# ECG.net
KiCad netlist of a schematic drawn in EAGLE
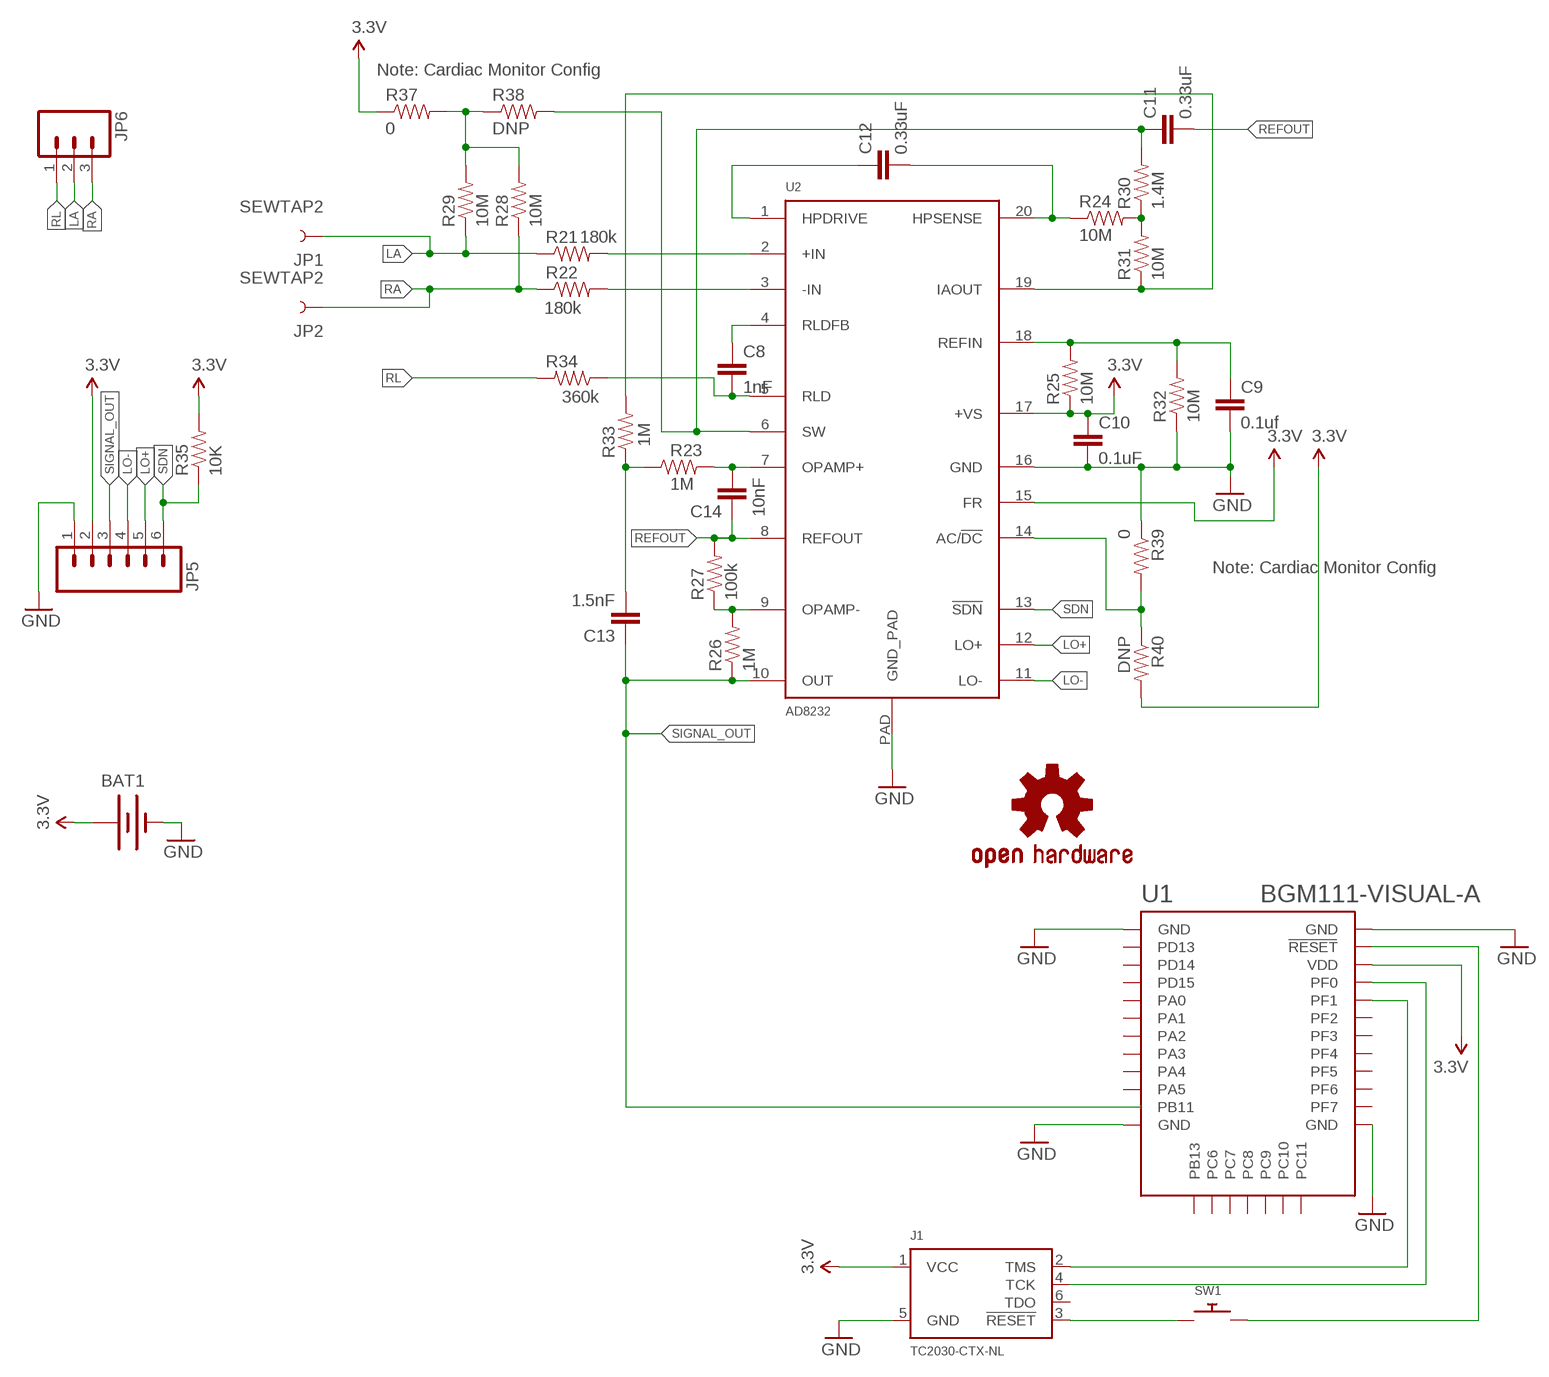
[diagram p0: schematic, sheet 1]

(export (version "E")
  (design (tool "Eeschema 10.0.6"))
  (components
    (comp (ref "BAT1")
      (value "BATTERY20SMD")
      (footprint "eagle-import:BATTCON_20MM")
      (libsource (lib "eagle-import") (part "BATTERY20SMD"))
    )
    (comp (ref "C8")
      (value "1nF")
      (footprint "eagle-import:0603-CAP")
      (libsource (lib "eagle-import") (part "CAP0603-CAP"))
    )
    (comp (ref "C9")
      (value "0.1uf")
      (footprint "eagle-import:0603-CAP")
      (libsource (lib "eagle-import") (part "CAP0603-CAP"))
    )
    (comp (ref "C10")
      (value "0.1uF")
      (footprint "eagle-import:0603-CAP")
      (libsource (lib "eagle-import") (part "CAP0603-CAP"))
    )
    (comp (ref "C11")
      (value "0.33uF")
      (footprint "eagle-import:0805")
      (libsource (lib "eagle-import") (part "CAP0805"))
    )
    (comp (ref "C12")
      (value "0.33uF")
      (footprint "eagle-import:0805")
      (libsource (lib "eagle-import") (part "CAP0805"))
    )
    (comp (ref "C13")
      (value "1.5nF")
      (footprint "eagle-import:0603-CAP")
      (libsource (lib "eagle-import") (part "CAP0603-CAP"))
    )
    (comp (ref "C14")
      (value "10nF")
      (footprint "eagle-import:0603-CAP")
      (libsource (lib "eagle-import") (part "CAP0603-CAP"))
    )
    (comp (ref "J1")
      (value "TC2030-CTX-NL")
      (footprint "eagle-import:TC2030-IDC-NL")
      (libsource (lib "eagle-import") (part "TC2030-CTX-NL"))
    )
    (comp (ref "JP1")
      (value "SEWTAP2")
      (footprint "eagle-import:PETAL-LONG-2")
      (libsource (lib "eagle-import") (part "SEWTAP2"))
    )
    (comp (ref "JP2")
      (value "SEWTAP2")
      (footprint "eagle-import:PETAL-LONG-2")
      (libsource (lib "eagle-import") (part "SEWTAP2"))
    )
    (comp (ref "JP5")
      (value "M06SIP")
      (footprint "eagle-import:1X06")
      (libsource (lib "eagle-import") (part "M06SIP"))
    )
    (comp (ref "JP6")
      (value "M03PTH")
      (footprint "eagle-import:1X03")
      (libsource (lib "eagle-import") (part "M03PTH"))
    )
    (comp (ref "LOGO3")
      (value "OSHW-LOGOS")
      (footprint "eagle-import:OSHW-LOGO-S")
      (libsource (lib "eagle-import") (part "OSHW-LOGOS"))
    )
    (comp (ref "R21")
      (value "180k")
      (footprint "eagle-import:0603-RES")
      (libsource (lib "eagle-import") (part "RESISTOR0603-RES"))
    )
    (comp (ref "R22")
      (value "180k")
      (footprint "eagle-import:0603-RES")
      (libsource (lib "eagle-import") (part "RESISTOR0603-RES"))
    )
    (comp (ref "R23")
      (value "1M")
      (footprint "eagle-import:0603-RES")
      (libsource (lib "eagle-import") (part "RESISTOR0603-RES"))
    )
    (comp (ref "R24")
      (value "10M")
      (footprint "eagle-import:0603-RES")
      (libsource (lib "eagle-import") (part "RESISTOR0603-RES"))
    )
    (comp (ref "R25")
      (value "10M")
      (footprint "eagle-import:0603-RES")
      (libsource (lib "eagle-import") (part "RESISTOR0603-RES"))
    )
    (comp (ref "R26")
      (value "1M")
      (footprint "eagle-import:0603-RES")
      (libsource (lib "eagle-import") (part "RESISTOR0603-RES"))
    )
    (comp (ref "R27")
      (value "100k")
      (footprint "eagle-import:0603-RES")
      (libsource (lib "eagle-import") (part "RESISTOR0603-RES"))
    )
    (comp (ref "R28")
      (value "10M")
      (footprint "eagle-import:0603-RES")
      (libsource (lib "eagle-import") (part "RESISTOR0603-RES"))
    )
    (comp (ref "R29")
      (value "10M")
      (footprint "eagle-import:0603-RES")
      (libsource (lib "eagle-import") (part "RESISTOR0603-RES"))
    )
    (comp (ref "R30")
      (value "1.4M")
      (footprint "eagle-import:0603-RES")
      (libsource (lib "eagle-import") (part "RESISTOR0603-RES"))
    )
    (comp (ref "R31")
      (value "10M")
      (footprint "eagle-import:0603-RES")
      (libsource (lib "eagle-import") (part "RESISTOR0603-RES"))
    )
    (comp (ref "R32")
      (value "10M")
      (footprint "eagle-import:0603-RES")
      (libsource (lib "eagle-import") (part "RESISTOR0603-RES"))
    )
    (comp (ref "R33")
      (value "1M")
      (footprint "eagle-import:0603-RES")
      (libsource (lib "eagle-import") (part "RESISTOR0603-RES"))
    )
    (comp (ref "R34")
      (value "360k")
      (footprint "eagle-import:0603-RES")
      (libsource (lib "eagle-import") (part "RESISTOR0603-RES"))
    )
    (comp (ref "R35")
      (value "10K")
      (footprint "eagle-import:0603-RES")
      (libsource (lib "eagle-import") (part "10KOHM1/10W1%(0603)0603"))
    )
    (comp (ref "R37")
      (value "0")
      (footprint "eagle-import:0603")
      (libsource (lib "eagle-import") (part "0OHM1/10W5%(0603)"))
    )
    (comp (ref "R38")
      (value "DNP")
      (footprint "eagle-import:0603")
      (libsource (lib "eagle-import") (part "0OHM1/10W5%(0603)"))
    )
    (comp (ref "R39")
      (value "0")
      (footprint "eagle-import:0603")
      (libsource (lib "eagle-import") (part "0OHM1/10W5%(0603)"))
    )
    (comp (ref "R40")
      (value "DNP")
      (footprint "eagle-import:0603")
      (libsource (lib "eagle-import") (part "0OHM1/10W5%(0603)"))
    )
    (comp (ref "SW1")
      (value "SWITCH_PUSHBUTTONSOFTTOUCHSMD_SJ")
      (footprint "eagle-import:PUSHBUTTON_SMD_SJ")
      (libsource (lib "eagle-import") (part "SWITCH_PUSHBUTTONSOFTTOUCHSMD_SJ"))
    )
    (comp (ref "U1")
      (value "BGM111-VISUAL-A")
      (footprint "eagle-import:BGM111-A")
      (libsource (lib "eagle-import") (part "BGM111-VISUAL-A"))
    )
    (comp (ref "U2")
      (value "AD8232")
      (footprint "eagle-import:LFCSP_20")
      (libsource (lib "eagle-import") (part "AD8232"))
    )
  )
  (nets
    (net (code "1") (name "3.3V") (class "Default")
      (node (ref "BAT1") (pin "1") (pinfunction "+_1") (pintype "power_in"))
      (node (ref "C10") (pin "1") (pinfunction "1_1") (pintype "passive"))
      (node (ref "J1") (pin "1") (pinfunction "VCC_1") (pintype "bidirectional"))
      (node (ref "JP5") (pin "2") (pinfunction "2_2") (pintype "passive"))
      (node (ref "R25") (pin "1") (pinfunction "1_1") (pintype "passive"))
      (node (ref "R35") (pin "2") (pinfunction "2_2") (pintype "passive"))
      (node (ref "R37") (pin "1") (pinfunction "1_1") (pintype "passive"))
      (node (ref "R40") (pin "2") (pinfunction "2_2") (pintype "passive"))
      (node (ref "U1") (pin "VDD") (pinfunction "VDD_VDD") (pintype "power_in"))
      (node (ref "U2") (pin "15") (pinfunction "FR_15") (pintype "bidirectional"))
      (node (ref "U2") (pin "17") (pinfunction "+VS_17") (pintype "bidirectional"))
    )
    (net (code "2") (name "GND") (class "Default")
      (node (ref "BAT1") (pin "2") (pinfunction "-_2") (pintype "power_in"))
      (node (ref "C10") (pin "2") (pinfunction "2_2") (pintype "passive"))
      (node (ref "C9") (pin "2") (pinfunction "2_2") (pintype "passive"))
      (node (ref "J1") (pin "5") (pinfunction "GND_5") (pintype "bidirectional"))
      (node (ref "JP5") (pin "1") (pinfunction "1_1") (pintype "passive"))
      (node (ref "R32") (pin "1") (pinfunction "1_1") (pintype "passive"))
      (node (ref "R39") (pin "1") (pinfunction "1_1") (pintype "passive"))
      (node (ref "U1") (pin "GND") (pinfunction "GND_GND") (pintype "power_in"))
      (node (ref "U1") (pin "GND@2") (pinfunction "GND_GND@2") (pintype "power_in"))
      (node (ref "U1") (pin "GND@3") (pinfunction "GND_GND@3") (pintype "power_in"))
      (node (ref "U1") (pin "GND@4") (pinfunction "GND_GND@4") (pintype "power_in"))
      (node (ref "U2") (pin "16") (pinfunction "GND_16") (pintype "bidirectional"))
      (node (ref "U2") (pin "PAD") (pinfunction "GND_PAD_PAD") (pintype "bidirectional"))
    )
    (net (code "3") (name "LA") (class "Default")
      (node (ref "JP1") (pin "1") (pinfunction "1_1") (pintype "bidirectional"))
      (node (ref "JP6") (pin "2") (pinfunction "2_2") (pintype "passive"))
      (node (ref "R21") (pin "1") (pinfunction "1_1") (pintype "passive"))
      (node (ref "R29") (pin "1") (pinfunction "1_1") (pintype "passive"))
    )
    (net (code "4") (name "LO+") (class "Default")
      (node (ref "JP5") (pin "5") (pinfunction "5_5") (pintype "passive"))
      (node (ref "U2") (pin "12") (pinfunction "LO+_12") (pintype "bidirectional"))
    )
    (net (code "5") (name "LO-") (class "Default")
      (node (ref "JP5") (pin "4") (pinfunction "4_4") (pintype "passive"))
      (node (ref "U2") (pin "11") (pinfunction "LO-_11") (pintype "bidirectional"))
    )
    (net (code "6") (name "Net-(C13-Pad2)") (class "Default")
      (node (ref "C13") (pin "2") (pinfunction "2_2") (pintype "passive"))
      (node (ref "R23") (pin "1") (pinfunction "1_1") (pintype "passive"))
      (node (ref "R33") (pin "1") (pinfunction "1_1") (pintype "passive"))
    )
    (net (code "7") (name "Net-(J1-TCK)") (class "Default")
      (node (ref "J1") (pin "4") (pinfunction "TCK_4") (pintype "bidirectional"))
      (node (ref "U1") (pin "PF0") (pinfunction "PF0_PF0") (pintype "bidirectional"))
    )
    (net (code "8") (name "Net-(J1-TMS)") (class "Default")
      (node (ref "J1") (pin "2") (pinfunction "TMS_2") (pintype "bidirectional"))
      (node (ref "U1") (pin "PF1") (pinfunction "PF1_PF1") (pintype "bidirectional"))
    )
    (net (code "9") (name "Net-(J1-~{RESET})") (class "Default")
      (node (ref "J1") (pin "3") (pinfunction "~{RESET}_3") (pintype "bidirectional"))
      (node (ref "SW1") (pin "P$1") (pinfunction "P$1_P$1") (pintype "passive"))
    )
    (net (code "10") (name "Net-(R24-Pad2)") (class "Default")
      (node (ref "R24") (pin "2") (pinfunction "2_2") (pintype "passive"))
      (node (ref "R30") (pin "1") (pinfunction "1_1") (pintype "passive"))
      (node (ref "R31") (pin "2") (pinfunction "2_2") (pintype "passive"))
    )
    (net (code "11") (name "Net-(R28-Pad2)") (class "Default")
      (node (ref "R28") (pin "2") (pinfunction "2_2") (pintype "passive"))
      (node (ref "R29") (pin "2") (pinfunction "2_2") (pintype "passive"))
      (node (ref "R37") (pin "2") (pinfunction "2_2") (pintype "passive"))
      (node (ref "R38") (pin "1") (pinfunction "1_1") (pintype "passive"))
    )
    (net (code "12") (name "Net-(SW1-PadP$2)") (class "Default")
      (node (ref "SW1") (pin "P$2") (pinfunction "P$2_P$2") (pintype "passive"))
      (node (ref "U1") (pin "RESET") (pinfunction "RESET_RESET") (pintype "input"))
    )
    (net (code "13") (name "Net-(U2-+IN)") (class "Default")
      (node (ref "R21") (pin "2") (pinfunction "2_2") (pintype "passive"))
      (node (ref "U2") (pin "2") (pinfunction "+IN_2") (pintype "bidirectional"))
    )
    (net (code "14") (name "Net-(U2--IN)") (class "Default")
      (node (ref "R22") (pin "2") (pinfunction "2_2") (pintype "passive"))
      (node (ref "U2") (pin "3") (pinfunction "-IN_3") (pintype "bidirectional"))
    )
    (net (code "15") (name "Net-(U2-AC{slash}~{DC})") (class "Default")
      (node (ref "R39") (pin "2") (pinfunction "2_2") (pintype "passive"))
      (node (ref "R40") (pin "1") (pinfunction "1_1") (pintype "passive"))
      (node (ref "U2") (pin "14") (pinfunction "AC/~{DC}_14") (pintype "bidirectional"))
    )
    (net (code "16") (name "Net-(U2-HPDRIVE)") (class "Default")
      (node (ref "C12") (pin "1") (pinfunction "1_1") (pintype "passive"))
      (node (ref "U2") (pin "1") (pinfunction "HPDRIVE_1") (pintype "bidirectional"))
    )
    (net (code "17") (name "Net-(U2-HPSENSE)") (class "Default")
      (node (ref "C12") (pin "2") (pinfunction "2_2") (pintype "passive"))
      (node (ref "R24") (pin "1") (pinfunction "1_1") (pintype "passive"))
      (node (ref "U2") (pin "20") (pinfunction "HPSENSE_20") (pintype "bidirectional"))
    )
    (net (code "18") (name "Net-(U2-IAOUT)") (class "Default")
      (node (ref "R31") (pin "1") (pinfunction "1_1") (pintype "passive"))
      (node (ref "R33") (pin "2") (pinfunction "2_2") (pintype "passive"))
      (node (ref "U2") (pin "19") (pinfunction "IAOUT_19") (pintype "bidirectional"))
    )
    (net (code "19") (name "Net-(U2-OPAMP+)") (class "Default")
      (node (ref "C14") (pin "2") (pinfunction "2_2") (pintype "passive"))
      (node (ref "R23") (pin "2") (pinfunction "2_2") (pintype "passive"))
      (node (ref "U2") (pin "7") (pinfunction "OPAMP+_7") (pintype "bidirectional"))
    )
    (net (code "20") (name "Net-(U2-OPAMP-)") (class "Default")
      (node (ref "R26") (pin "2") (pinfunction "2_2") (pintype "passive"))
      (node (ref "R27") (pin "1") (pinfunction "1_1") (pintype "passive"))
      (node (ref "U2") (pin "9") (pinfunction "OPAMP-_9") (pintype "bidirectional"))
    )
    (net (code "21") (name "Net-(U2-REFIN)") (class "Default")
      (node (ref "C9") (pin "1") (pinfunction "1_1") (pintype "passive"))
      (node (ref "R25") (pin "2") (pinfunction "2_2") (pintype "passive"))
      (node (ref "R32") (pin "2") (pinfunction "2_2") (pintype "passive"))
      (node (ref "U2") (pin "18") (pinfunction "REFIN_18") (pintype "bidirectional"))
    )
    (net (code "22") (name "Net-(U2-RLD)") (class "Default")
      (node (ref "C8") (pin "2") (pinfunction "2_2") (pintype "passive"))
      (node (ref "R34") (pin "1") (pinfunction "1_1") (pintype "passive"))
      (node (ref "U2") (pin "5") (pinfunction "RLD_5") (pintype "bidirectional"))
    )
    (net (code "23") (name "Net-(U2-RLDFB)") (class "Default")
      (node (ref "C8") (pin "1") (pinfunction "1_1") (pintype "passive"))
      (node (ref "U2") (pin "4") (pinfunction "RLDFB_4") (pintype "bidirectional"))
    )
    (net (code "24") (name "Net-(U2-SW)") (class "Default")
      (node (ref "C11") (pin "1") (pinfunction "1_1") (pintype "passive"))
      (node (ref "R30") (pin "2") (pinfunction "2_2") (pintype "passive"))
      (node (ref "R38") (pin "2") (pinfunction "2_2") (pintype "passive"))
      (node (ref "U2") (pin "6") (pinfunction "SW_6") (pintype "bidirectional"))
    )
    (net (code "25") (name "RA") (class "Default")
      (node (ref "JP2") (pin "1") (pinfunction "1_1") (pintype "bidirectional"))
      (node (ref "JP6") (pin "3") (pinfunction "3_3") (pintype "passive"))
      (node (ref "R22") (pin "1") (pinfunction "1_1") (pintype "passive"))
      (node (ref "R28") (pin "1") (pinfunction "1_1") (pintype "passive"))
    )
    (net (code "26") (name "REFOUT") (class "Default")
      (node (ref "C11") (pin "2") (pinfunction "2_2") (pintype "passive"))
      (node (ref "C14") (pin "1") (pinfunction "1_1") (pintype "passive"))
      (node (ref "R27") (pin "2") (pinfunction "2_2") (pintype "passive"))
      (node (ref "U2") (pin "8") (pinfunction "REFOUT_8") (pintype "bidirectional"))
    )
    (net (code "27") (name "RL") (class "Default")
      (node (ref "JP6") (pin "1") (pinfunction "1_1") (pintype "passive"))
      (node (ref "R34") (pin "2") (pinfunction "2_2") (pintype "passive"))
    )
    (net (code "28") (name "SDN") (class "Default")
      (node (ref "JP5") (pin "6") (pinfunction "6_6") (pintype "passive"))
      (node (ref "R35") (pin "1") (pinfunction "1_1") (pintype "passive"))
      (node (ref "U2") (pin "13") (pinfunction "~{SDN}_13") (pintype "bidirectional"))
    )
    (net (code "29") (name "SIGNAL_OUT") (class "Default")
      (node (ref "C13") (pin "1") (pinfunction "1_1") (pintype "passive"))
      (node (ref "JP5") (pin "3") (pinfunction "3_3") (pintype "passive"))
      (node (ref "R26") (pin "1") (pinfunction "1_1") (pintype "passive"))
      (node (ref "U2") (pin "10") (pinfunction "OUT_10") (pintype "bidirectional"))
    )
    (net (code "30") (name "unconnected-(J1-TDO-Pad6)") (class "Default")
      (node (ref "J1") (pin "6") (pinfunction "TDO_6") (pintype "bidirectional"))
    )
    (net (code "31") (name "unconnected-(U1-PadPA0)") (class "Default")
      (node (ref "U1") (pin "PA0") (pinfunction "PA0_PA0") (pintype "bidirectional"))
    )
    (net (code "32") (name "unconnected-(U1-PadPA1)") (class "Default")
      (node (ref "U1") (pin "PA1") (pinfunction "PA1_PA1") (pintype "bidirectional"))
    )
    (net (code "33") (name "unconnected-(U1-PadPA2)") (class "Default")
      (node (ref "U1") (pin "PA2") (pinfunction "PA2_PA2") (pintype "bidirectional"))
    )
    (net (code "34") (name "unconnected-(U1-PadPA3)") (class "Default")
      (node (ref "U1") (pin "PA3") (pinfunction "PA3_PA3") (pintype "bidirectional"))
    )
    (net (code "35") (name "unconnected-(U1-PadPA4)") (class "Default")
      (node (ref "U1") (pin "PA4") (pinfunction "PA4_PA4") (pintype "bidirectional"))
    )
    (net (code "36") (name "unconnected-(U1-PadPA5)") (class "Default")
      (node (ref "U1") (pin "PA5") (pinfunction "PA5_PA5") (pintype "bidirectional"))
    )
    (net (code "37") (name "unconnected-(U1-PadPB11)") (class "Default")
      (node (ref "U1") (pin "PB11") (pinfunction "PB11_PB11") (pintype "bidirectional"))
    )
    (net (code "38") (name "unconnected-(U1-PadPB13)") (class "Default")
      (node (ref "U1") (pin "PB13") (pinfunction "PB13_PB13") (pintype "bidirectional"))
    )
    (net (code "39") (name "unconnected-(U1-PadPC6)") (class "Default")
      (node (ref "U1") (pin "PC6") (pinfunction "PC6_PC6") (pintype "bidirectional"))
    )
    (net (code "40") (name "unconnected-(U1-PadPC7)") (class "Default")
      (node (ref "U1") (pin "PC7") (pinfunction "PC7_PC7") (pintype "bidirectional"))
    )
    (net (code "41") (name "unconnected-(U1-PadPC8)") (class "Default")
      (node (ref "U1") (pin "PC8") (pinfunction "PC8_PC8") (pintype "bidirectional"))
    )
    (net (code "42") (name "unconnected-(U1-PadPC9)") (class "Default")
      (node (ref "U1") (pin "PC9") (pinfunction "PC9_PC9") (pintype "bidirectional"))
    )
    (net (code "43") (name "unconnected-(U1-PadPC10)") (class "Default")
      (node (ref "U1") (pin "PC10") (pinfunction "PC10_PC10") (pintype "bidirectional"))
    )
    (net (code "44") (name "unconnected-(U1-PadPC11)") (class "Default")
      (node (ref "U1") (pin "PC11") (pinfunction "PC11_PC11") (pintype "bidirectional"))
    )
    (net (code "45") (name "unconnected-(U1-PadPD13)") (class "Default")
      (node (ref "U1") (pin "PD13") (pinfunction "PD13_PD13") (pintype "bidirectional"))
    )
    (net (code "46") (name "unconnected-(U1-PadPD14)") (class "Default")
      (node (ref "U1") (pin "PD14") (pinfunction "PD14_PD14") (pintype "bidirectional"))
    )
    (net (code "47") (name "unconnected-(U1-PadPD15)") (class "Default")
      (node (ref "U1") (pin "PD15") (pinfunction "PD15_PD15") (pintype "bidirectional"))
    )
    (net (code "48") (name "unconnected-(U1-PadPF2)") (class "Default")
      (node (ref "U1") (pin "PF2") (pinfunction "PF2_PF2") (pintype "bidirectional"))
    )
    (net (code "49") (name "unconnected-(U1-PadPF3)") (class "Default")
      (node (ref "U1") (pin "PF3") (pinfunction "PF3_PF3") (pintype "bidirectional"))
    )
    (net (code "50") (name "unconnected-(U1-PadPF4)") (class "Default")
      (node (ref "U1") (pin "PF4") (pinfunction "PF4_PF4") (pintype "bidirectional"))
    )
    (net (code "51") (name "unconnected-(U1-PadPF5)") (class "Default")
      (node (ref "U1") (pin "PF5") (pinfunction "PF5_PF5") (pintype "bidirectional"))
    )
    (net (code "52") (name "unconnected-(U1-PadPF6)") (class "Default")
      (node (ref "U1") (pin "PF6") (pinfunction "PF6_PF6") (pintype "bidirectional"))
    )
    (net (code "53") (name "unconnected-(U1-PadPF7)") (class "Default")
      (node (ref "U1") (pin "PF7") (pinfunction "PF7_PF7") (pintype "bidirectional"))
    )
  )
)
